# Microcontroller.net
KiCad netlist of a schematic drawn in Altium Designer
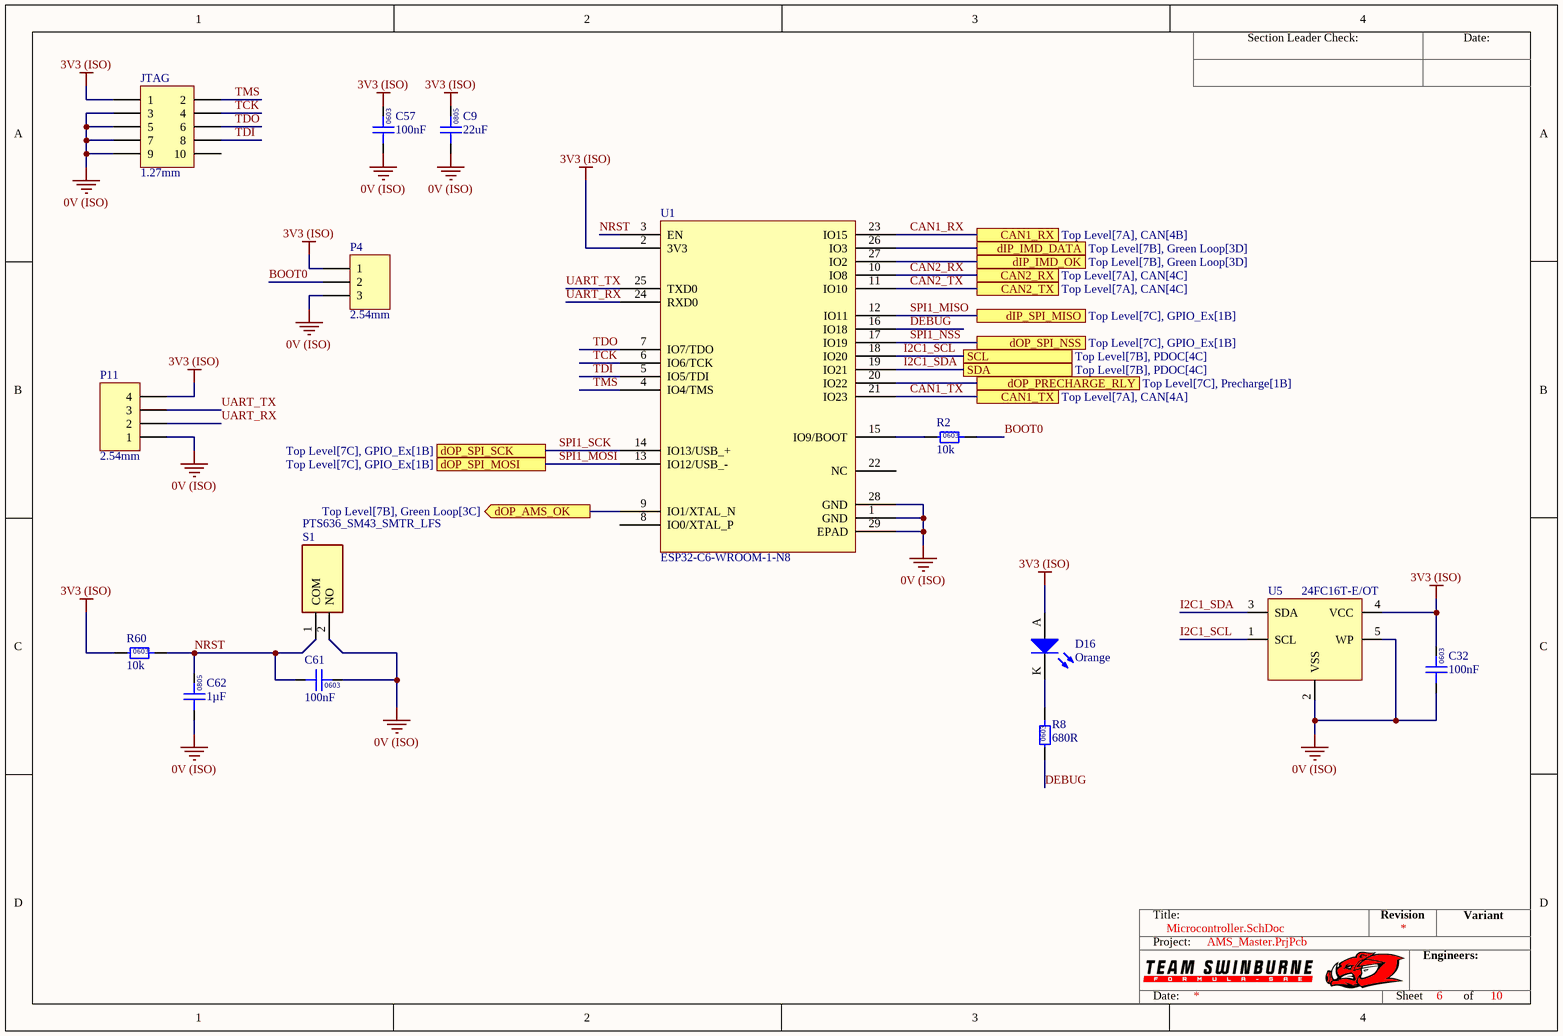
[diagram p0: Microcontroller.SchDoc]

(export (version "E")
  (design (tool "Eeschema 10.0.6"))
  (components
    (comp (ref "C9")
      (value "22uF")
      (footprint "0805")
      (fields
        (field (name "PART NUMBER") "GRM21BR61A226ME51L")
        (field (name "MANUFACTURER") "muRata")
        (field (name "TOLERANCE") "20%")
      )
      (libsource (lib "ts_standard_library") (part "Capacitor 0805"))
    )
    (comp (ref "C32")
      (value "100nF")
      (footprint "0603")
      (fields
        (field (name "PART NUMBER") "CL10B104KC8NNNC")
        (field (name "MANUFACTURER") "Samsung Electro-Mechanics")
        (field (name "TOLERANCE") "±10%")
      )
      (libsource (lib "ts_standard_library") (part "Capacitor 0603"))
    )
    (comp (ref "C57")
      (value "100nF")
      (footprint "0603")
      (fields
        (field (name "PART NUMBER") "GCM188L81H104KA57D")
        (field (name "MANUFACTURER") "muRata")
        (field (name "TOLERANCE") "±10%")
      )
      (libsource (lib "ts_standard_library") (part "Capacitor 0603"))
    )
    (comp (ref "C61")
      (value "100nF")
      (footprint "0603")
      (fields
        (field (name "PART NUMBER") "GCM188L81H104KA57D")
        (field (name "MANUFACTURER") "muRata")
        (field (name "TOLERANCE") "±10%")
      )
      (libsource (lib "ts_standard_library") (part "Capacitor 0603"))
    )
    (comp (ref "C62")
      (value "1µF")
      (footprint "0805")
      (fields
        (field (name "PART NUMBER") "GCM21BR71H105KA03L")
        (field (name "MANUFACTURER") "muRata")
        (field (name "TOLERANCE") "±10%")
      )
      (libsource (lib "ts_standard_library") (part "Capacitor 0805"))
    )
    (comp (ref "D16")
      (value "Orange")
      (footprint "0805 LED")
      (description "Orange LED Indication - Discrete 1.75V 0805 (2012 Metric)")
      (fields (field (name "PART NUMBER") "SML-211DTT86") (field (name "MANUFACTURER") "ROHM Semiconductor"))
      (libsource (lib "ts_standard_library") (part "LED"))
    )
    (comp (ref "JTAG")
      (value "1.27mm")
      (footprint "3221-10-0300-00")
      (fields
        (field (name "PART NUMBER") "SMD 1.27mm Header 2x5 (3221-10-0300-00)")
        (field (name "CONTACT") "NA")
      )
      (libsource (lib "ts_standard_connectors") (part "Header 2x5"))
    )
    (comp (ref "P4")
      (value "2.54mm")
      (footprint "TH 2.54mm Header 1x3")
      (fields (field (name "PART NUMBER") "TH 2.54mm Header 1x3") (field (name "CONTACT") "NA"))
      (libsource (lib "ts_standard_connectors") (part "Header 1x3"))
    )
    (comp (ref "P11")
      (value "2.54mm")
      (footprint "TH 2.54mm Header 1x4")
      (fields (field (name "PART NUMBER") "TH 2.54mm Header 1x4") (field (name "CONTACT") "NA"))
      (libsource (lib "ts_standard_connectors") (part "Header 1x4"))
    )
    (comp (ref "R2")
      (value "10k")
      (footprint "0603")
      (fields
        (field (name "PART NUMBER") "RC0603FR-0710KL")
        (field (name "MANUFACTURER") "YAGEO")
        (field (name "TOLERANCE") "0.01")
      )
      (libsource (lib "ts_standard_library") (part "Resistor 0603"))
    )
    (comp (ref "R8")
      (value "680R")
      (footprint "0603")
      (fields
        (field (name "PART NUMBER") "RC0603JR-13680RL")
        (field (name "MANUFACTURER") "YAGEO")
        (field (name "TOLERANCE") "0.01")
      )
      (libsource (lib "ts_standard_library") (part "Resistor 0603"))
    )
    (comp (ref "R60")
      (value "10k")
      (footprint "0603")
      (fields
        (field (name "PART NUMBER") "RC0603FR-0710KL")
        (field (name "MANUFACTURER") "YAGEO")
        (field (name "TOLERANCE") "0.01")
      )
      (libsource (lib "ts_standard_library") (part "Resistor 0603"))
    )
    (comp (ref "S1")
      (value "PTS636_SM43_SMTR_LFS")
      (footprint "SamacSys:PTS636SM43SMTRLFS")
      (description "Switch")
      (fields
        (field (name "MANUFACTURER_PART_NUMBER") "PTS636 SM43 SMTR LFS")
        (field (name "MOUSER PART NUMBER") "611-PTS636SM43SMTRLF")
      )
      (libsource (lib "*") (part "PTS636_SM43_SMTR_LFS"))
    )
    (comp (ref "U1")
      (value "ESP32-C6-WROOM-1-N8")
      (footprint "ESP32-C6-WROOM-1-N8")
      (description "RF TXRX MOD BT WIFI PCB TH SMD")
      (fields (field (name "MANUFACTURER") "Espressif"))
      (libsource (lib "ts_standard_library") (part "ESP32-C6-WROOM-1-N8"))
    )
    (comp (ref "U5")
      (value "24FC16T-E/OT")
      (footprint "MCP SOT-23-5")
      (description "IC EEPROM 16KBIT I2C SOT23-5")
      (fields
        (field (name "MANUFACTURER") "Microchip Technology")
        (field (name "DIGIKEY PART NUMBER") "150-24FC16T-E/OTCT-ND")
      )
      (libsource (lib "ts_standard_library") (part "24FC16T-E/OT"))
    )
  )
  (nets
    (net (code "1") (name "/BOOT0") (class "Default")
      (node (ref "P4") (pin "2") (pinfunction "2_2") (pintype "passive"))
      (node (ref "R2") (pin "2") (pinfunction "2_2") (pintype "passive"))
    )
    (net (code "2") (name "/CAN1_RX") (class "Default")
      (node (ref "U1") (pin "23") (pinfunction "IO15_23") (pintype "passive"))
    )
    (net (code "3") (name "/CAN1_TX") (class "Default")
      (node (ref "U1") (pin "21") (pinfunction "IO23_21") (pintype "passive"))
    )
    (net (code "4") (name "/CAN2_RX") (class "Default")
      (node (ref "U1") (pin "10") (pinfunction "IO8_10") (pintype "passive"))
    )
    (net (code "5") (name "/CAN2_TX") (class "Default")
      (node (ref "U1") (pin "11") (pinfunction "IO10_11") (pintype "passive"))
    )
    (net (code "6") (name "/DEBUG") (class "Default")
      (node (ref "R8") (pin "1") (pinfunction "1_1") (pintype "passive"))
      (node (ref "U1") (pin "16") (pinfunction "IO18_16") (pintype "passive"))
    )
    (net (code "7") (name "/I2C1_SCL") (class "Default")
      (node (ref "U1") (pin "18") (pinfunction "IO20_18") (pintype "passive"))
      (node (ref "U5") (pin "1") (pinfunction "SCL_1") (pintype "passive"))
    )
    (net (code "8") (name "/I2C1_SDA") (class "Default")
      (node (ref "U1") (pin "19") (pinfunction "IO21_19") (pintype "passive"))
      (node (ref "U5") (pin "3") (pinfunction "SDA_3") (pintype "passive"))
    )
    (net (code "9") (name "/NRST") (class "Default")
      (node (ref "C61") (pin "1") (pinfunction "1_1") (pintype "passive"))
      (node (ref "C62") (pin "2") (pinfunction "2_2") (pintype "passive"))
      (node (ref "R60") (pin "2") (pinfunction "2_2") (pintype "passive"))
      (node (ref "S1") (pin "1") (pinfunction "COM_1") (pintype "passive"))
      (node (ref "U1") (pin "3") (pinfunction "EN_3") (pintype "passive"))
    )
    (net (code "10") (name "/SPI1_MISO") (class "Default")
      (node (ref "U1") (pin "12") (pinfunction "IO11_12") (pintype "passive"))
    )
    (net (code "11") (name "/SPI1_MOSI") (class "Default")
      (node (ref "U1") (pin "13") (pinfunction "IO12/USB_-_13") (pintype "passive"))
    )
    (net (code "12") (name "/SPI1_NSS") (class "Default")
      (node (ref "U1") (pin "17") (pinfunction "IO19_17") (pintype "passive"))
    )
    (net (code "13") (name "/SPI1_SCK") (class "Default")
      (node (ref "U1") (pin "14") (pinfunction "IO13/USB_+_14") (pintype "passive"))
    )
    (net (code "14") (name "/TCK") (class "Default")
      (node (ref "JTAG") (pin "4") (pinfunction "4_4") (pintype "passive"))
      (node (ref "U1") (pin "6") (pinfunction "IO6/TCK_6") (pintype "passive"))
    )
    (net (code "15") (name "/TDI") (class "Default")
      (node (ref "JTAG") (pin "8") (pinfunction "8_8") (pintype "passive"))
      (node (ref "U1") (pin "5") (pinfunction "IO5/TDI_5") (pintype "passive"))
    )
    (net (code "16") (name "/TDO") (class "Default")
      (node (ref "JTAG") (pin "6") (pinfunction "6_6") (pintype "passive"))
      (node (ref "U1") (pin "7") (pinfunction "IO7/TDO_7") (pintype "passive"))
    )
    (net (code "17") (name "/TMS") (class "Default")
      (node (ref "JTAG") (pin "2") (pinfunction "2_2") (pintype "passive"))
      (node (ref "U1") (pin "4") (pinfunction "IO4/TMS_4") (pintype "passive"))
    )
    (net (code "18") (name "/UART_RX") (class "Default")
      (node (ref "P11") (pin "2") (pinfunction "2_2") (pintype "passive"))
      (node (ref "U1") (pin "24") (pinfunction "RXD0_24") (pintype "passive"))
    )
    (net (code "19") (name "/UART_TX") (class "Default")
      (node (ref "P11") (pin "3") (pinfunction "3_3") (pintype "passive"))
      (node (ref "U1") (pin "25") (pinfunction "TXD0_25") (pintype "passive"))
    )
    (net (code "20") (name "/dIP_IMD_DATA") (class "Default")
      (node (ref "U1") (pin "26") (pinfunction "IO3_26") (pintype "passive"))
    )
    (net (code "21") (name "/dIP_IMD_OK") (class "Default")
      (node (ref "U1") (pin "27") (pinfunction "IO2_27") (pintype "passive"))
    )
    (net (code "22") (name "/dOP_AMS_OK") (class "Default")
      (node (ref "U1") (pin "9") (pinfunction "IO1/XTAL_N_9") (pintype "passive"))
    )
    (net (code "23") (name "/dOP_PRECHARGE_RLY") (class "Default")
      (node (ref "U1") (pin "20") (pinfunction "IO22_20") (pintype "passive"))
    )
    (net (code "24") (name "0V (ISO)") (class "Default")
      (node (ref "C32") (pin "1") (pinfunction "1_1") (pintype "passive"))
      (node (ref "C57") (pin "1") (pinfunction "1_1") (pintype "passive"))
      (node (ref "C61") (pin "2") (pinfunction "2_2") (pintype "passive"))
      (node (ref "C62") (pin "1") (pinfunction "1_1") (pintype "passive"))
      (node (ref "C9") (pin "1") (pinfunction "1_1") (pintype "passive"))
      (node (ref "JTAG") (pin "3") (pinfunction "3_3") (pintype "passive"))
      (node (ref "JTAG") (pin "5") (pinfunction "5_5") (pintype "passive"))
      (node (ref "JTAG") (pin "7") (pinfunction "7_7") (pintype "passive"))
      (node (ref "JTAG") (pin "9") (pinfunction "9_9") (pintype "passive"))
      (node (ref "P11") (pin "1") (pinfunction "1_1") (pintype "passive"))
      (node (ref "P4") (pin "3") (pinfunction "3_3") (pintype "passive"))
      (node (ref "S1") (pin "2") (pinfunction "NO_2") (pintype "passive"))
      (node (ref "U1") (pin "1") (pinfunction "GND_1") (pintype "passive"))
      (node (ref "U1") (pin "28") (pinfunction "GND_28") (pintype "passive"))
      (node (ref "U1") (pin "29") (pinfunction "EPAD_29") (pintype "passive"))
      (node (ref "U5") (pin "2") (pinfunction "VSS_2") (pintype "passive"))
      (node (ref "U5") (pin "5") (pinfunction "WP_5") (pintype "passive"))
    )
    (net (code "25") (name "3V3 (ISO)") (class "Default")
      (node (ref "C32") (pin "2") (pinfunction "2_2") (pintype "passive"))
      (node (ref "C57") (pin "2") (pinfunction "2_2") (pintype "passive"))
      (node (ref "C9") (pin "2") (pinfunction "2_2") (pintype "passive"))
      (node (ref "D16") (pin "A") (pinfunction "A_A") (pintype "passive"))
      (node (ref "JTAG") (pin "1") (pinfunction "1_1") (pintype "passive"))
      (node (ref "P11") (pin "4") (pinfunction "4_4") (pintype "passive"))
      (node (ref "P4") (pin "1") (pinfunction "1_1") (pintype "passive"))
      (node (ref "R60") (pin "1") (pinfunction "1_1") (pintype "passive"))
      (node (ref "U1") (pin "2") (pinfunction "3V3_2") (pintype "passive"))
      (node (ref "U5") (pin "4") (pinfunction "VCC_4") (pintype "passive"))
    )
    (net (code "26") (name "Net-(D16-PadK)") (class "Default")
      (node (ref "D16") (pin "K") (pinfunction "K_K") (pintype "passive"))
      (node (ref "R8") (pin "2") (pinfunction "2_2") (pintype "passive"))
    )
    (net (code "27") (name "Net-(U1-IO9{slash}BOOT)") (class "Default")
      (node (ref "R2") (pin "1") (pinfunction "1_1") (pintype "passive"))
      (node (ref "U1") (pin "15") (pinfunction "IO9/BOOT_15") (pintype "passive"))
    )
    (net (code "28") (name "unconnected-(JTAG-Pad10)") (class "Default")
      (node (ref "JTAG") (pin "10") (pinfunction "10_10") (pintype "passive"))
    )
    (net (code "29") (name "unconnected-(U1-IO0{slash}XTAL_P-Pad8)") (class "Default")
      (node (ref "U1") (pin "8") (pinfunction "IO0/XTAL_P_8") (pintype "passive"))
    )
    (net (code "30") (name "unconnected-(U1-NC-Pad22)") (class "Default")
      (node (ref "U1") (pin "22") (pinfunction "NC_22") (pintype "passive"))
    )
  )
)
